# 02-cpu_connect.net
KiCad netlist of a schematic drawn in Altium Designer
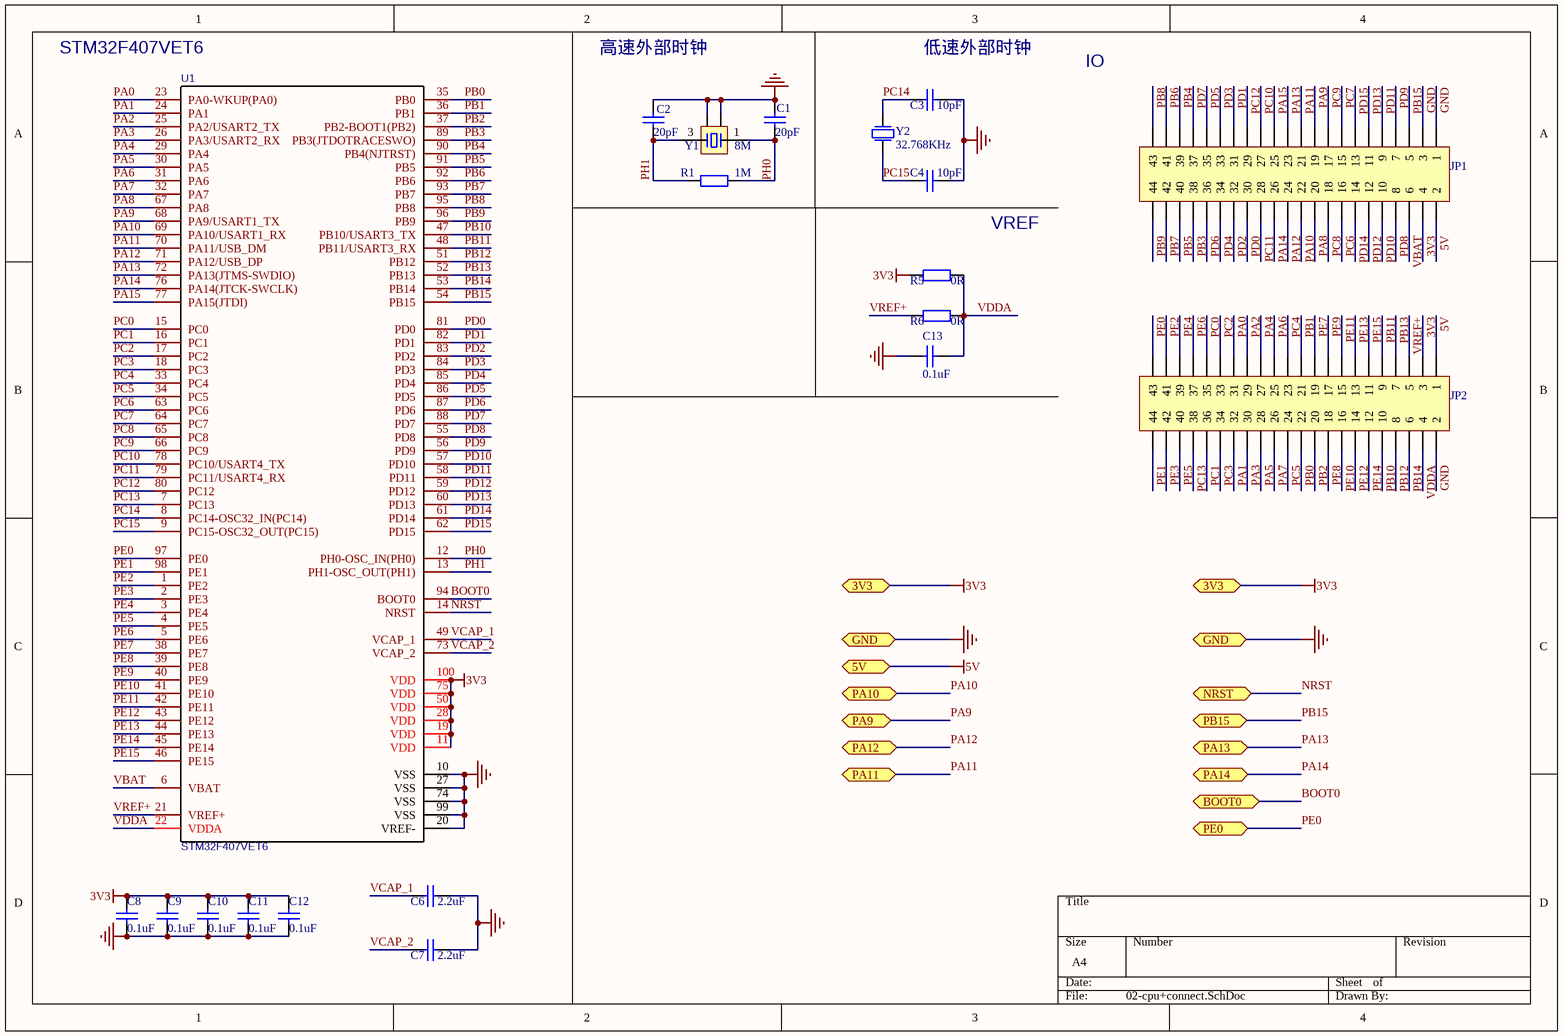
[diagram p0: 02-cpu+connect.SchDoc]

(export (version "E")
  (design (tool "Eeschema 10.0.6"))
  (components
    (comp (ref "C1") (value "20pF") (footprint "C 0402_L") (libsource (lib "Schlib1") (part "Cap")))
    (comp (ref "C2") (value "20pF") (footprint "C 0402_L") (libsource (lib "Schlib1") (part "Cap")))
    (comp (ref "C3") (value "10pF") (footprint "C 0402_L") (libsource (lib "Schlib1") (part "Cap")))
    (comp (ref "C4") (value "10pF") (footprint "C 0402_L") (libsource (lib "Schlib1") (part "Cap")))
    (comp (ref "C6") (value "2.2uF") (footprint "C 0402_L") (libsource (lib "Schlib1") (part "Cap")))
    (comp (ref "C7") (value "2.2uF") (footprint "C 0402_L") (libsource (lib "Schlib1") (part "Cap")))
    (comp (ref "C8") (value "0.1uF") (footprint "C 0402_L") (libsource (lib "Schlib1") (part "Cap")))
    (comp (ref "C9") (value "0.1uF") (footprint "C 0402_L") (libsource (lib "Schlib1") (part "Cap")))
    (comp (ref "C10") (value "0.1uF") (footprint "C 0402_L") (libsource (lib "Schlib1") (part "Cap")))
    (comp (ref "C11") (value "0.1uF") (footprint "C 0402_L") (libsource (lib "Schlib1") (part "Cap")))
    (comp (ref "C12") (value "0.1uF") (footprint "C 0402_L") (libsource (lib "Schlib1") (part "Cap")))
    (comp (ref "C13") (value "0.1uF") (footprint "C 0402_L") (libsource (lib "Schlib1") (part "Cap")))
    (comp (ref "JP1")
      (value "Header 2x22")
      (footprint "HDR2.54-LI-2x22P")
      (description "2x22P接插件")
      (libsource (lib "Schlib1") (part "Header 2x22"))
    )
    (comp (ref "JP2")
      (value "Header 2x22")
      (footprint "HDR2.54-LI-2x22P")
      (description "2x22P接插件")
      (libsource (lib "Schlib1") (part "Header 2x22"))
    )
    (comp (ref "R1") (value "1M") (footprint "R 0402_L") (libsource (lib "Schlib1") (part "Res")))
    (comp (ref "R5") (value "0R") (footprint "R 0402_L") (libsource (lib "Schlib1") (part "Res")))
    (comp (ref "R6") (value "0R") (footprint "R 0402_L") (libsource (lib "Schlib1") (part "Res")))
    (comp (ref "U1")
      (value "STM32F407VET6")
      (footprint "LQFP100 14x14_N")
      (fields (field (name "BOM_SUPPLIER PART") "C28730") (field (name "SUBPART_NO") "1"))
      (libsource (lib "Schlib1") (part "STM32F407VET6"))
    )
    (comp (ref "Y1")
      (value "8M")
      (footprint "OSC 3225-4P")
      (description "4脚无源晶振")
      (libsource (lib "Schlib1") (part "XTAL-4P"))
    )
    (comp (ref "Y2")
      (value "32.768KHz")
      (footprint "FC135-3.2X1.5")
      (libsource (lib "Schlib1") (part "XTAL-2P"))
    )
  )
  (nets
    (net (code "1") (name "/BOOT0") (class "Default")
      (node (ref "U1") (pin "94") (pinfunction "BOOT0_94") (pintype "passive"))
    )
    (net (code "2") (name "/NRST") (class "Default")
      (node (ref "U1") (pin "14") (pinfunction "NRST_14") (pintype "passive"))
    )
    (net (code "3") (name "/PA0") (class "Default")
      (node (ref "JP2") (pin "31") (pinfunction "31_31") (pintype "passive"))
      (node (ref "U1") (pin "23") (pinfunction "PA0-WKUP(PA0)_23") (pintype "passive"))
    )
    (net (code "4") (name "/PA1") (class "Default")
      (node (ref "JP2") (pin "32") (pinfunction "32_32") (pintype "passive"))
      (node (ref "U1") (pin "24") (pinfunction "PA1_24") (pintype "passive"))
    )
    (net (code "5") (name "/PA2") (class "Default")
      (node (ref "JP2") (pin "29") (pinfunction "29_29") (pintype "passive"))
      (node (ref "U1") (pin "25") (pinfunction "PA2/USART2_TX_25") (pintype "passive"))
    )
    (net (code "6") (name "/PA3") (class "Default")
      (node (ref "JP2") (pin "30") (pinfunction "30_30") (pintype "passive"))
      (node (ref "U1") (pin "26") (pinfunction "PA3/USART2_RX_26") (pintype "passive"))
    )
    (net (code "7") (name "/PA4") (class "Default")
      (node (ref "JP2") (pin "27") (pinfunction "27_27") (pintype "passive"))
      (node (ref "U1") (pin "29") (pinfunction "PA4_29") (pintype "passive"))
    )
    (net (code "8") (name "/PA5") (class "Default")
      (node (ref "JP2") (pin "28") (pinfunction "28_28") (pintype "passive"))
      (node (ref "U1") (pin "30") (pinfunction "PA5_30") (pintype "passive"))
    )
    (net (code "9") (name "/PA6") (class "Default")
      (node (ref "JP2") (pin "25") (pinfunction "25_25") (pintype "passive"))
      (node (ref "U1") (pin "31") (pinfunction "PA6_31") (pintype "passive"))
    )
    (net (code "10") (name "/PA7") (class "Default")
      (node (ref "JP2") (pin "26") (pinfunction "26_26") (pintype "passive"))
      (node (ref "U1") (pin "32") (pinfunction "PA7_32") (pintype "passive"))
    )
    (net (code "11") (name "/PA8") (class "Default")
      (node (ref "JP1") (pin "20") (pinfunction "20_20") (pintype "passive"))
      (node (ref "U1") (pin "67") (pinfunction "PA8_67") (pintype "passive"))
    )
    (net (code "12") (name "/PA9") (class "Default")
      (node (ref "JP1") (pin "19") (pinfunction "19_19") (pintype "passive"))
      (node (ref "U1") (pin "68") (pinfunction "PA9/USART1_TX_68") (pintype "passive"))
    )
    (net (code "13") (name "/PA10") (class "Default")
      (node (ref "JP1") (pin "22") (pinfunction "22_22") (pintype "passive"))
      (node (ref "U1") (pin "69") (pinfunction "PA10/USART1_RX_69") (pintype "passive"))
    )
    (net (code "14") (name "/PA11") (class "Default")
      (node (ref "JP1") (pin "21") (pinfunction "21_21") (pintype "passive"))
      (node (ref "U1") (pin "70") (pinfunction "PA11/USB_DM_70") (pintype "passive"))
    )
    (net (code "15") (name "/PA12") (class "Default")
      (node (ref "JP1") (pin "24") (pinfunction "24_24") (pintype "passive"))
      (node (ref "U1") (pin "71") (pinfunction "PA12/USB_DP_71") (pintype "passive"))
    )
    (net (code "16") (name "/PA13") (class "Default")
      (node (ref "JP1") (pin "23") (pinfunction "23_23") (pintype "passive"))
      (node (ref "U1") (pin "72") (pinfunction "PA13(JTMS-SWDIO)_72") (pintype "passive"))
    )
    (net (code "17") (name "/PA14") (class "Default")
      (node (ref "JP1") (pin "26") (pinfunction "26_26") (pintype "passive"))
      (node (ref "U1") (pin "76") (pinfunction "PA14(JTCK-SWCLK)_76") (pintype "passive"))
    )
    (net (code "18") (name "/PA15") (class "Default")
      (node (ref "JP1") (pin "25") (pinfunction "25_25") (pintype "passive"))
      (node (ref "U1") (pin "77") (pinfunction "PA15(JTDI)_77") (pintype "passive"))
    )
    (net (code "19") (name "/PB0") (class "Default")
      (node (ref "JP2") (pin "22") (pinfunction "22_22") (pintype "passive"))
      (node (ref "U1") (pin "35") (pinfunction "PB0_35") (pintype "passive"))
    )
    (net (code "20") (name "/PB1") (class "Default")
      (node (ref "JP2") (pin "21") (pinfunction "21_21") (pintype "passive"))
      (node (ref "U1") (pin "36") (pinfunction "PB1_36") (pintype "passive"))
    )
    (net (code "21") (name "/PB2") (class "Default")
      (node (ref "JP2") (pin "20") (pinfunction "20_20") (pintype "passive"))
      (node (ref "U1") (pin "37") (pinfunction "PB2-BOOT1(PB2)_37") (pintype "passive"))
    )
    (net (code "22") (name "/PB3") (class "Default")
      (node (ref "JP1") (pin "38") (pinfunction "38_38") (pintype "passive"))
      (node (ref "U1") (pin "89") (pinfunction "PB3(JTDOTRACESWO)_89") (pintype "passive"))
    )
    (net (code "23") (name "/PB4") (class "Default")
      (node (ref "JP1") (pin "39") (pinfunction "39_39") (pintype "passive"))
      (node (ref "U1") (pin "90") (pinfunction "PB4(NJTRST)_90") (pintype "passive"))
    )
    (net (code "24") (name "/PB5") (class "Default")
      (node (ref "JP1") (pin "40") (pinfunction "40_40") (pintype "passive"))
      (node (ref "U1") (pin "91") (pinfunction "PB5_91") (pintype "passive"))
    )
    (net (code "25") (name "/PB6") (class "Default")
      (node (ref "JP1") (pin "41") (pinfunction "41_41") (pintype "passive"))
      (node (ref "U1") (pin "92") (pinfunction "PB6_92") (pintype "passive"))
    )
    (net (code "26") (name "/PB7") (class "Default")
      (node (ref "JP1") (pin "42") (pinfunction "42_42") (pintype "passive"))
      (node (ref "U1") (pin "93") (pinfunction "PB7_93") (pintype "passive"))
    )
    (net (code "27") (name "/PB8") (class "Default")
      (node (ref "JP1") (pin "43") (pinfunction "43_43") (pintype "passive"))
      (node (ref "U1") (pin "95") (pinfunction "PB8_95") (pintype "passive"))
    )
    (net (code "28") (name "/PB9") (class "Default")
      (node (ref "JP1") (pin "44") (pinfunction "44_44") (pintype "passive"))
      (node (ref "U1") (pin "96") (pinfunction "PB9_96") (pintype "passive"))
    )
    (net (code "29") (name "/PB10") (class "Default")
      (node (ref "JP2") (pin "10") (pinfunction "10_10") (pintype "passive"))
      (node (ref "U1") (pin "47") (pinfunction "PB10/USART3_TX_47") (pintype "passive"))
    )
    (net (code "30") (name "/PB11") (class "Default")
      (node (ref "JP2") (pin "9") (pinfunction "9_9") (pintype "passive"))
      (node (ref "U1") (pin "48") (pinfunction "PB11/USART3_RX_48") (pintype "passive"))
    )
    (net (code "31") (name "/PB12") (class "Default")
      (node (ref "JP2") (pin "8") (pinfunction "8_8") (pintype "passive"))
      (node (ref "U1") (pin "51") (pinfunction "PB12_51") (pintype "passive"))
    )
    (net (code "32") (name "/PB13") (class "Default")
      (node (ref "JP2") (pin "7") (pinfunction "7_7") (pintype "passive"))
      (node (ref "U1") (pin "52") (pinfunction "PB13_52") (pintype "passive"))
    )
    (net (code "33") (name "/PB14") (class "Default")
      (node (ref "JP2") (pin "6") (pinfunction "6_6") (pintype "passive"))
      (node (ref "U1") (pin "53") (pinfunction "PB14_53") (pintype "passive"))
    )
    (net (code "34") (name "/PB15") (class "Default")
      (node (ref "JP1") (pin "5") (pinfunction "5_5") (pintype "passive"))
      (node (ref "U1") (pin "54") (pinfunction "PB15_54") (pintype "passive"))
    )
    (net (code "35") (name "/PC0") (class "Default")
      (node (ref "JP2") (pin "35") (pinfunction "35_35") (pintype "passive"))
      (node (ref "U1") (pin "15") (pinfunction "PC0_15") (pintype "passive"))
    )
    (net (code "36") (name "/PC1") (class "Default")
      (node (ref "JP2") (pin "36") (pinfunction "36_36") (pintype "passive"))
      (node (ref "U1") (pin "16") (pinfunction "PC1_16") (pintype "passive"))
    )
    (net (code "37") (name "/PC2") (class "Default")
      (node (ref "JP2") (pin "33") (pinfunction "33_33") (pintype "passive"))
      (node (ref "U1") (pin "17") (pinfunction "PC2_17") (pintype "passive"))
    )
    (net (code "38") (name "/PC3") (class "Default")
      (node (ref "JP2") (pin "34") (pinfunction "34_34") (pintype "passive"))
      (node (ref "U1") (pin "18") (pinfunction "PC3_18") (pintype "passive"))
    )
    (net (code "39") (name "/PC4") (class "Default")
      (node (ref "JP2") (pin "23") (pinfunction "23_23") (pintype "passive"))
      (node (ref "U1") (pin "33") (pinfunction "PC4_33") (pintype "passive"))
    )
    (net (code "40") (name "/PC5") (class "Default")
      (node (ref "JP2") (pin "24") (pinfunction "24_24") (pintype "passive"))
      (node (ref "U1") (pin "34") (pinfunction "PC5_34") (pintype "passive"))
    )
    (net (code "41") (name "/PC6") (class "Default")
      (node (ref "JP1") (pin "16") (pinfunction "16_16") (pintype "passive"))
      (node (ref "U1") (pin "63") (pinfunction "PC6_63") (pintype "passive"))
    )
    (net (code "42") (name "/PC7") (class "Default")
      (node (ref "JP1") (pin "15") (pinfunction "15_15") (pintype "passive"))
      (node (ref "U1") (pin "64") (pinfunction "PC7_64") (pintype "passive"))
    )
    (net (code "43") (name "/PC8") (class "Default")
      (node (ref "JP1") (pin "18") (pinfunction "18_18") (pintype "passive"))
      (node (ref "U1") (pin "65") (pinfunction "PC8_65") (pintype "passive"))
    )
    (net (code "44") (name "/PC9") (class "Default")
      (node (ref "JP1") (pin "17") (pinfunction "17_17") (pintype "passive"))
      (node (ref "U1") (pin "66") (pinfunction "PC9_66") (pintype "passive"))
    )
    (net (code "45") (name "/PC10") (class "Default")
      (node (ref "JP1") (pin "27") (pinfunction "27_27") (pintype "passive"))
      (node (ref "U1") (pin "78") (pinfunction "PC10/USART4_TX_78") (pintype "passive"))
    )
    (net (code "46") (name "/PC11") (class "Default")
      (node (ref "JP1") (pin "28") (pinfunction "28_28") (pintype "passive"))
      (node (ref "U1") (pin "79") (pinfunction "PC11/USART4_RX_79") (pintype "passive"))
    )
    (net (code "47") (name "/PC12") (class "Default")
      (node (ref "JP1") (pin "29") (pinfunction "29_29") (pintype "passive"))
      (node (ref "U1") (pin "80") (pinfunction "PC12_80") (pintype "passive"))
    )
    (net (code "48") (name "/PC13") (class "Default")
      (node (ref "JP2") (pin "38") (pinfunction "38_38") (pintype "passive"))
      (node (ref "U1") (pin "7") (pinfunction "PC13_7") (pintype "passive"))
    )
    (net (code "49") (name "/PC14") (class "Default")
      (node (ref "C3") (pin "2") (pinfunction "2_2") (pintype "passive"))
      (node (ref "U1") (pin "8") (pinfunction "PC14-OSC32_IN(PC14)_8") (pintype "passive"))
      (node (ref "Y2") (pin "1") (pinfunction "P1_1") (pintype "passive"))
    )
    (net (code "50") (name "/PC15") (class "Default")
      (node (ref "C4") (pin "2") (pinfunction "2_2") (pintype "passive"))
      (node (ref "U1") (pin "9") (pinfunction "PC15-OSC32_OUT(PC15)_9") (pintype "passive"))
      (node (ref "Y2") (pin "2") (pinfunction "P2_2") (pintype "passive"))
    )
    (net (code "51") (name "/PD0") (class "Default")
      (node (ref "JP1") (pin "30") (pinfunction "30_30") (pintype "passive"))
      (node (ref "U1") (pin "81") (pinfunction "PD0_81") (pintype "passive"))
    )
    (net (code "52") (name "/PD1") (class "Default")
      (node (ref "JP1") (pin "31") (pinfunction "31_31") (pintype "passive"))
      (node (ref "U1") (pin "82") (pinfunction "PD1_82") (pintype "passive"))
    )
    (net (code "53") (name "/PD2") (class "Default")
      (node (ref "JP1") (pin "32") (pinfunction "32_32") (pintype "passive"))
      (node (ref "U1") (pin "83") (pinfunction "PD2_83") (pintype "passive"))
    )
    (net (code "54") (name "/PD3") (class "Default")
      (node (ref "JP1") (pin "33") (pinfunction "33_33") (pintype "passive"))
      (node (ref "U1") (pin "84") (pinfunction "PD3_84") (pintype "passive"))
    )
    (net (code "55") (name "/PD4") (class "Default")
      (node (ref "JP1") (pin "34") (pinfunction "34_34") (pintype "passive"))
      (node (ref "U1") (pin "85") (pinfunction "PD4_85") (pintype "passive"))
    )
    (net (code "56") (name "/PD5") (class "Default")
      (node (ref "JP1") (pin "35") (pinfunction "35_35") (pintype "passive"))
      (node (ref "U1") (pin "86") (pinfunction "PD5_86") (pintype "passive"))
    )
    (net (code "57") (name "/PD6") (class "Default")
      (node (ref "JP1") (pin "36") (pinfunction "36_36") (pintype "passive"))
      (node (ref "U1") (pin "87") (pinfunction "PD6_87") (pintype "passive"))
    )
    (net (code "58") (name "/PD7") (class "Default")
      (node (ref "JP1") (pin "37") (pinfunction "37_37") (pintype "passive"))
      (node (ref "U1") (pin "88") (pinfunction "PD7_88") (pintype "passive"))
    )
    (net (code "59") (name "/PD8") (class "Default")
      (node (ref "JP1") (pin "8") (pinfunction "8_8") (pintype "passive"))
      (node (ref "U1") (pin "55") (pinfunction "PD8_55") (pintype "passive"))
    )
    (net (code "60") (name "/PD9") (class "Default")
      (node (ref "JP1") (pin "7") (pinfunction "7_7") (pintype "passive"))
      (node (ref "U1") (pin "56") (pinfunction "PD9_56") (pintype "passive"))
    )
    (net (code "61") (name "/PD10") (class "Default")
      (node (ref "JP1") (pin "10") (pinfunction "10_10") (pintype "passive"))
      (node (ref "U1") (pin "57") (pinfunction "PD10_57") (pintype "passive"))
    )
    (net (code "62") (name "/PD11") (class "Default")
      (node (ref "JP1") (pin "9") (pinfunction "9_9") (pintype "passive"))
      (node (ref "U1") (pin "58") (pinfunction "PD11_58") (pintype "passive"))
    )
    (net (code "63") (name "/PD12") (class "Default")
      (node (ref "JP1") (pin "12") (pinfunction "12_12") (pintype "passive"))
      (node (ref "U1") (pin "59") (pinfunction "PD12_59") (pintype "passive"))
    )
    (net (code "64") (name "/PD13") (class "Default")
      (node (ref "JP1") (pin "11") (pinfunction "11_11") (pintype "passive"))
      (node (ref "U1") (pin "60") (pinfunction "PD13_60") (pintype "passive"))
    )
    (net (code "65") (name "/PD14") (class "Default")
      (node (ref "JP1") (pin "14") (pinfunction "14_14") (pintype "passive"))
      (node (ref "U1") (pin "61") (pinfunction "PD14_61") (pintype "passive"))
    )
    (net (code "66") (name "/PD15") (class "Default")
      (node (ref "JP1") (pin "13") (pinfunction "13_13") (pintype "passive"))
      (node (ref "U1") (pin "62") (pinfunction "PD15_62") (pintype "passive"))
    )
    (net (code "67") (name "/PE0") (class "Default")
      (node (ref "JP2") (pin "43") (pinfunction "43_43") (pintype "passive"))
      (node (ref "U1") (pin "97") (pinfunction "PE0_97") (pintype "passive"))
    )
    (net (code "68") (name "/PE1") (class "Default")
      (node (ref "JP2") (pin "44") (pinfunction "44_44") (pintype "passive"))
      (node (ref "U1") (pin "98") (pinfunction "PE1_98") (pintype "passive"))
    )
    (net (code "69") (name "/PE2") (class "Default")
      (node (ref "JP2") (pin "41") (pinfunction "41_41") (pintype "passive"))
      (node (ref "U1") (pin "1") (pinfunction "PE2_1") (pintype "passive"))
    )
    (net (code "70") (name "/PE3") (class "Default")
      (node (ref "JP2") (pin "42") (pinfunction "42_42") (pintype "passive"))
      (node (ref "U1") (pin "2") (pinfunction "PE3_2") (pintype "passive"))
    )
    (net (code "71") (name "/PE4") (class "Default")
      (node (ref "JP2") (pin "39") (pinfunction "39_39") (pintype "passive"))
      (node (ref "U1") (pin "3") (pinfunction "PE4_3") (pintype "passive"))
    )
    (net (code "72") (name "/PE5") (class "Default")
      (node (ref "JP2") (pin "40") (pinfunction "40_40") (pintype "passive"))
      (node (ref "U1") (pin "4") (pinfunction "PE5_4") (pintype "passive"))
    )
    (net (code "73") (name "/PE6") (class "Default")
      (node (ref "JP2") (pin "37") (pinfunction "37_37") (pintype "passive"))
      (node (ref "U1") (pin "5") (pinfunction "PE6_5") (pintype "passive"))
    )
    (net (code "74") (name "/PE7") (class "Default")
      (node (ref "JP2") (pin "19") (pinfunction "19_19") (pintype "passive"))
      (node (ref "U1") (pin "38") (pinfunction "PE7_38") (pintype "passive"))
    )
    (net (code "75") (name "/PE8") (class "Default")
      (node (ref "JP2") (pin "18") (pinfunction "18_18") (pintype "passive"))
      (node (ref "U1") (pin "39") (pinfunction "PE8_39") (pintype "passive"))
    )
    (net (code "76") (name "/PE9") (class "Default")
      (node (ref "JP2") (pin "17") (pinfunction "17_17") (pintype "passive"))
      (node (ref "U1") (pin "40") (pinfunction "PE9_40") (pintype "passive"))
    )
    (net (code "77") (name "/PE10") (class "Default")
      (node (ref "JP2") (pin "16") (pinfunction "16_16") (pintype "passive"))
      (node (ref "U1") (pin "41") (pinfunction "PE10_41") (pintype "passive"))
    )
    (net (code "78") (name "/PE11") (class "Default")
      (node (ref "JP2") (pin "15") (pinfunction "15_15") (pintype "passive"))
      (node (ref "U1") (pin "42") (pinfunction "PE11_42") (pintype "passive"))
    )
    (net (code "79") (name "/PE12") (class "Default")
      (node (ref "JP2") (pin "14") (pinfunction "14_14") (pintype "passive"))
      (node (ref "U1") (pin "43") (pinfunction "PE12_43") (pintype "passive"))
    )
    (net (code "80") (name "/PE13") (class "Default")
      (node (ref "JP2") (pin "13") (pinfunction "13_13") (pintype "passive"))
      (node (ref "U1") (pin "44") (pinfunction "PE13_44") (pintype "passive"))
    )
    (net (code "81") (name "/PE14") (class "Default")
      (node (ref "JP2") (pin "12") (pinfunction "12_12") (pintype "passive"))
      (node (ref "U1") (pin "45") (pinfunction "PE14_45") (pintype "passive"))
    )
    (net (code "82") (name "/PE15") (class "Default")
      (node (ref "JP2") (pin "11") (pinfunction "11_11") (pintype "passive"))
      (node (ref "U1") (pin "46") (pinfunction "PE15_46") (pintype "passive"))
    )
    (net (code "83") (name "/PH0") (class "Default")
      (node (ref "C1") (pin "2") (pinfunction "2_2") (pintype "passive"))
      (node (ref "R1") (pin "1") (pinfunction "1_1") (pintype "passive"))
      (node (ref "U1") (pin "12") (pinfunction "PH0-OSC_IN(PH0)_12") (pintype "passive"))
      (node (ref "Y1") (pin "1") (pinfunction "1_1") (pintype "passive"))
    )
    (net (code "84") (name "/PH1") (class "Default")
      (node (ref "C2") (pin "2") (pinfunction "2_2") (pintype "passive"))
      (node (ref "R1") (pin "2") (pinfunction "2_2") (pintype "passive"))
      (node (ref "U1") (pin "13") (pinfunction "PH1-OSC_OUT(PH1)_13") (pintype "passive"))
      (node (ref "Y1") (pin "3") (pinfunction "3_3") (pintype "passive"))
    )
    (net (code "85") (name "/VBAT") (class "Default")
      (node (ref "JP1") (pin "6") (pinfunction "6_6") (pintype "passive"))
      (node (ref "U1") (pin "6") (pinfunction "VBAT_6") (pintype "passive"))
    )
    (net (code "86") (name "/VCAP_1") (class "Default")
      (node (ref "C6") (pin "2") (pinfunction "2_2") (pintype "passive"))
      (node (ref "U1") (pin "49") (pinfunction "VCAP_1_49") (pintype "passive"))
    )
    (net (code "87") (name "/VCAP_2") (class "Default")
      (node (ref "C7") (pin "2") (pinfunction "2_2") (pintype "passive"))
      (node (ref "U1") (pin "73") (pinfunction "VCAP_2_73") (pintype "passive"))
    )
    (net (code "88") (name "/VDDA") (class "Default")
      (node (ref "C13") (pin "2") (pinfunction "2_2") (pintype "passive"))
      (node (ref "JP2") (pin "4") (pinfunction "4_4") (pintype "passive"))
      (node (ref "R5") (pin "1") (pinfunction "1_1") (pintype "passive"))
      (node (ref "R6") (pin "1") (pinfunction "1_1") (pintype "passive"))
      (node (ref "U1") (pin "22") (pinfunction "VDDA_22") (pintype "passive"))
    )
    (net (code "89") (name "/VREF+") (class "Default")
      (node (ref "JP2") (pin "5") (pinfunction "5_5") (pintype "passive"))
      (node (ref "R6") (pin "2") (pinfunction "2_2") (pintype "passive"))
      (node (ref "U1") (pin "21") (pinfunction "VREF+_21") (pintype "passive"))
    )
    (net (code "90") (name "3V3") (class "Default")
      (node (ref "C10") (pin "1") (pinfunction "1_1") (pintype "passive"))
      (node (ref "C11") (pin "1") (pinfunction "1_1") (pintype "passive"))
      (node (ref "C12") (pin "1") (pinfunction "1_1") (pintype "passive"))
      (node (ref "C8") (pin "1") (pinfunction "1_1") (pintype "passive"))
      (node (ref "C9") (pin "1") (pinfunction "1_1") (pintype "passive"))
      (node (ref "JP1") (pin "4") (pinfunction "4_4") (pintype "passive"))
      (node (ref "JP2") (pin "3") (pinfunction "3_3") (pintype "passive"))
      (node (ref "R5") (pin "2") (pinfunction "2_2") (pintype "passive"))
      (node (ref "U1") (pin "100") (pinfunction "VDD_100") (pintype "passive"))
      (node (ref "U1") (pin "11") (pinfunction "VDD_11") (pintype "passive"))
      (node (ref "U1") (pin "19") (pinfunction "VDD_19") (pintype "passive"))
      (node (ref "U1") (pin "28") (pinfunction "VDD_28") (pintype "passive"))
      (node (ref "U1") (pin "50") (pinfunction "VDD_50") (pintype "passive"))
      (node (ref "U1") (pin "75") (pinfunction "VDD_75") (pintype "passive"))
    )
    (net (code "91") (name "5V") (class "Default")
      (node (ref "JP1") (pin "2") (pinfunction "2_2") (pintype "passive"))
      (node (ref "JP2") (pin "1") (pinfunction "1_1") (pintype "passive"))
    )
    (net (code "92") (name "GND") (class "Default")
      (node (ref "C1") (pin "1") (pinfunction "1_1") (pintype "passive"))
      (node (ref "C10") (pin "2") (pinfunction "2_2") (pintype "passive"))
      (node (ref "C11") (pin "2") (pinfunction "2_2") (pintype "passive"))
      (node (ref "C12") (pin "2") (pinfunction "2_2") (pintype "passive"))
      (node (ref "C13") (pin "1") (pinfunction "1_1") (pintype "passive"))
      (node (ref "C2") (pin "1") (pinfunction "1_1") (pintype "passive"))
      (node (ref "C3") (pin "1") (pinfunction "1_1") (pintype "passive"))
      (node (ref "C4") (pin "1") (pinfunction "1_1") (pintype "passive"))
      (node (ref "C6") (pin "1") (pinfunction "1_1") (pintype "passive"))
      (node (ref "C7") (pin "1") (pinfunction "1_1") (pintype "passive"))
      (node (ref "C8") (pin "2") (pinfunction "2_2") (pintype "passive"))
      (node (ref "C9") (pin "2") (pinfunction "2_2") (pintype "passive"))
      (node (ref "JP1") (pin "1") (pinfunction "1_1") (pintype "passive"))
      (node (ref "JP1") (pin "3") (pinfunction "3_3") (pintype "passive"))
      (node (ref "JP2") (pin "2") (pinfunction "2_2") (pintype "passive"))
      (node (ref "U1") (pin "10") (pinfunction "VSS_10") (pintype "passive"))
      (node (ref "U1") (pin "20") (pinfunction "VREF-_20") (pintype "passive"))
      (node (ref "U1") (pin "27") (pinfunction "VSS_27") (pintype "passive"))
      (node (ref "U1") (pin "74") (pinfunction "VSS_74") (pintype "passive"))
      (node (ref "U1") (pin "99") (pinfunction "VSS_99") (pintype "passive"))
      (node (ref "Y1") (pin "2") (pinfunction "2_2") (pintype "passive"))
      (node (ref "Y1") (pin "4") (pinfunction "4_4") (pintype "passive"))
    )
  )
)
